# fat-pepper-preamp.net
KiCad netlist of a schematic drawn in EAGLE
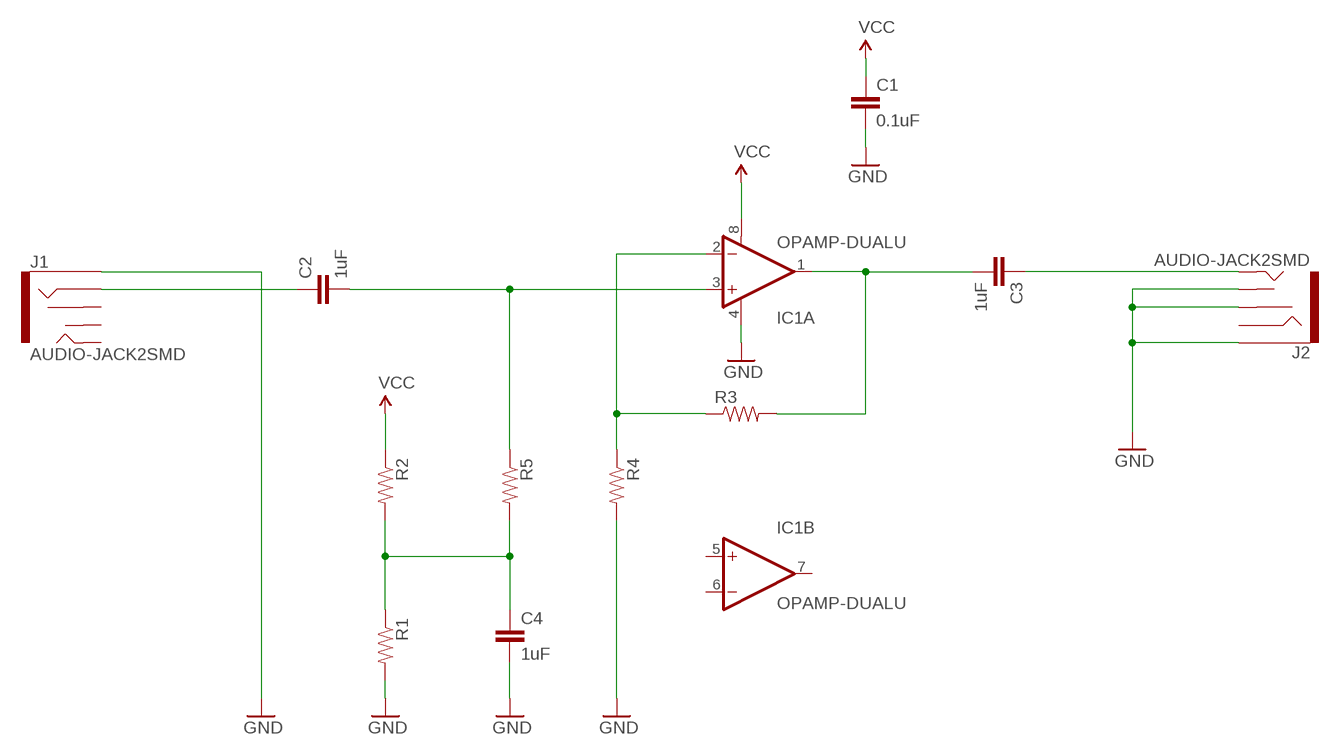
[diagram p0: schematic, sheet 1]

(export (version "E")
  (design (tool "Eeschema 10.0.6"))
  (components
    (comp (ref "C1")
      (value "0.1uF")
      (footprint "eagle-import:0402-CAP")
      (libsource (lib "eagle-import") (part "0.1UF-16V(+-10%)(0402)"))
    )
    (comp (ref "C2")
      (value "1uF")
      (footprint "eagle-import:0603-CAP")
      (libsource (lib "eagle-import") (part "CAP0603-CAP"))
    )
    (comp (ref "C3")
      (value "1uF")
      (footprint "eagle-import:0603-CAP")
      (libsource (lib "eagle-import") (part "CAP0603-CAP"))
    )
    (comp (ref "C4")
      (value "1uF")
      (footprint "eagle-import:0603-CAP")
      (libsource (lib "eagle-import") (part "CAP0603-CAP"))
    )
    (comp (ref "IC1")
      (value "OPAMP-DUALU")
      (footprint "eagle-import:SO08")
      (libsource (lib "eagle-import") (part "OPAMP-DUALU"))
    )
    (comp (ref "J1")
      (value "AUDIO-JACK2SMD")
      (footprint "eagle-import:AUDIO-JACK-3.5MM-SMD")
      (libsource (lib "eagle-import") (part "AUDIO-JACK2SMD"))
    )
    (comp (ref "J2")
      (value "AUDIO-JACK2SMD")
      (footprint "eagle-import:AUDIO-JACK-3.5MM-SMD")
      (libsource (lib "eagle-import") (part "AUDIO-JACK2SMD"))
    )
    (comp (ref "R1")
      (value "RESISTOR0603-RES")
      (footprint "eagle-import:0603-RES")
      (libsource (lib "eagle-import") (part "RESISTOR0603-RES"))
    )
    (comp (ref "R2")
      (value "RESISTOR0603-RES")
      (footprint "eagle-import:0603-RES")
      (libsource (lib "eagle-import") (part "RESISTOR0603-RES"))
    )
    (comp (ref "R3")
      (value "RESISTOR0603-RES")
      (footprint "eagle-import:0603-RES")
      (libsource (lib "eagle-import") (part "RESISTOR0603-RES"))
    )
    (comp (ref "R4")
      (value "RESISTOR0603-RES")
      (footprint "eagle-import:0603-RES")
      (libsource (lib "eagle-import") (part "RESISTOR0603-RES"))
    )
    (comp (ref "R5")
      (value "RESISTOR0603-RES")
      (footprint "eagle-import:0603-RES")
      (libsource (lib "eagle-import") (part "RESISTOR0603-RES"))
    )
  )
  (nets
    (net (code "1") (name "GND") (class "Default")
      (node (ref "C1") (pin "2") (pinfunction "2_2") (pintype "passive"))
      (node (ref "C4") (pin "2") (pinfunction "2_2") (pintype "passive"))
      (node (ref "IC1") (pin "4") (pinfunction "V-_4") (pintype "power_in"))
      (node (ref "J1") (pin "SLEEVE") (pinfunction "SLEEVE_SLEEVE") (pintype "bidirectional"))
      (node (ref "J2") (pin "RSH") (pinfunction "RSH_RSH") (pintype "bidirectional"))
      (node (ref "J2") (pin "SLEEVE") (pinfunction "SLEEVE_SLEEVE") (pintype "bidirectional"))
      (node (ref "J2") (pin "TSH") (pinfunction "TSH_TSH") (pintype "bidirectional"))
      (node (ref "R1") (pin "2") (pinfunction "2_2") (pintype "passive"))
      (node (ref "R4") (pin "2") (pinfunction "2_2") (pintype "passive"))
    )
    (net (code "2") (name "Net-(C2-Pad1)") (class "Default")
      (node (ref "C2") (pin "1") (pinfunction "1_1") (pintype "passive"))
      (node (ref "J1") (pin "RING") (pinfunction "RING_RING") (pintype "bidirectional"))
    )
    (net (code "3") (name "Net-(C3-Pad1)") (class "Default")
      (node (ref "C3") (pin "1") (pinfunction "1_1") (pintype "passive"))
      (node (ref "J2") (pin "TIP") (pinfunction "TIP_TIP") (pintype "bidirectional"))
    )
    (net (code "4") (name "Net-(C4-Pad1)") (class "Default")
      (node (ref "C4") (pin "1") (pinfunction "1_1") (pintype "passive"))
      (node (ref "R1") (pin "1") (pinfunction "1_1") (pintype "passive"))
      (node (ref "R2") (pin "2") (pinfunction "2_2") (pintype "passive"))
      (node (ref "R5") (pin "2") (pinfunction "2_2") (pintype "passive"))
    )
    (net (code "5") (name "Net-(IC1A-+IN)") (class "Default")
      (node (ref "C2") (pin "2") (pinfunction "2_2") (pintype "passive"))
      (node (ref "IC1") (pin "3") (pinfunction "+IN_3") (pintype "input"))
      (node (ref "R5") (pin "1") (pinfunction "1_1") (pintype "passive"))
    )
    (net (code "6") (name "Net-(IC1A--IN)") (class "Default")
      (node (ref "IC1") (pin "2") (pinfunction "-IN_2") (pintype "input"))
      (node (ref "R3") (pin "1") (pinfunction "1_1") (pintype "passive"))
      (node (ref "R4") (pin "1") (pinfunction "1_1") (pintype "passive"))
    )
    (net (code "7") (name "Net-(IC1A-OUT)") (class "Default")
      (node (ref "C3") (pin "2") (pinfunction "2_2") (pintype "passive"))
      (node (ref "IC1") (pin "1") (pinfunction "OUT_1") (pintype "output"))
      (node (ref "R3") (pin "2") (pinfunction "2_2") (pintype "passive"))
    )
    (net (code "8") (name "VCC") (class "Default")
      (node (ref "C1") (pin "1") (pinfunction "1_1") (pintype "passive"))
      (node (ref "IC1") (pin "8") (pinfunction "V+_8") (pintype "power_in"))
      (node (ref "R2") (pin "1") (pinfunction "1_1") (pintype "passive"))
    )
    (net (code "9") (name "unconnected-(IC1B-+IN-Pad5)") (class "Default")
      (node (ref "IC1") (pin "5") (pinfunction "+IN_5") (pintype "input"))
    )
    (net (code "10") (name "unconnected-(IC1B--IN-Pad6)") (class "Default")
      (node (ref "IC1") (pin "6") (pinfunction "-IN_6") (pintype "input"))
    )
    (net (code "11") (name "unconnected-(IC1B-OUT-Pad7)") (class "Default")
      (node (ref "IC1") (pin "7") (pinfunction "OUT_7") (pintype "output"))
    )
    (net (code "12") (name "unconnected-(J1-PadRSH)") (class "Default")
      (node (ref "J1") (pin "RSH") (pinfunction "RSH_RSH") (pintype "bidirectional"))
    )
    (net (code "13") (name "unconnected-(J1-PadTIP)") (class "Default")
      (node (ref "J1") (pin "TIP") (pinfunction "TIP_TIP") (pintype "bidirectional"))
    )
    (net (code "14") (name "unconnected-(J1-PadTSH)") (class "Default")
      (node (ref "J1") (pin "TSH") (pinfunction "TSH_TSH") (pintype "bidirectional"))
    )
    (net (code "15") (name "unconnected-(J2-PadRING)") (class "Default")
      (node (ref "J2") (pin "RING") (pinfunction "RING_RING") (pintype "bidirectional"))
    )
  )
)
